# Top.net
KiCad netlist of a schematic drawn in EAGLE
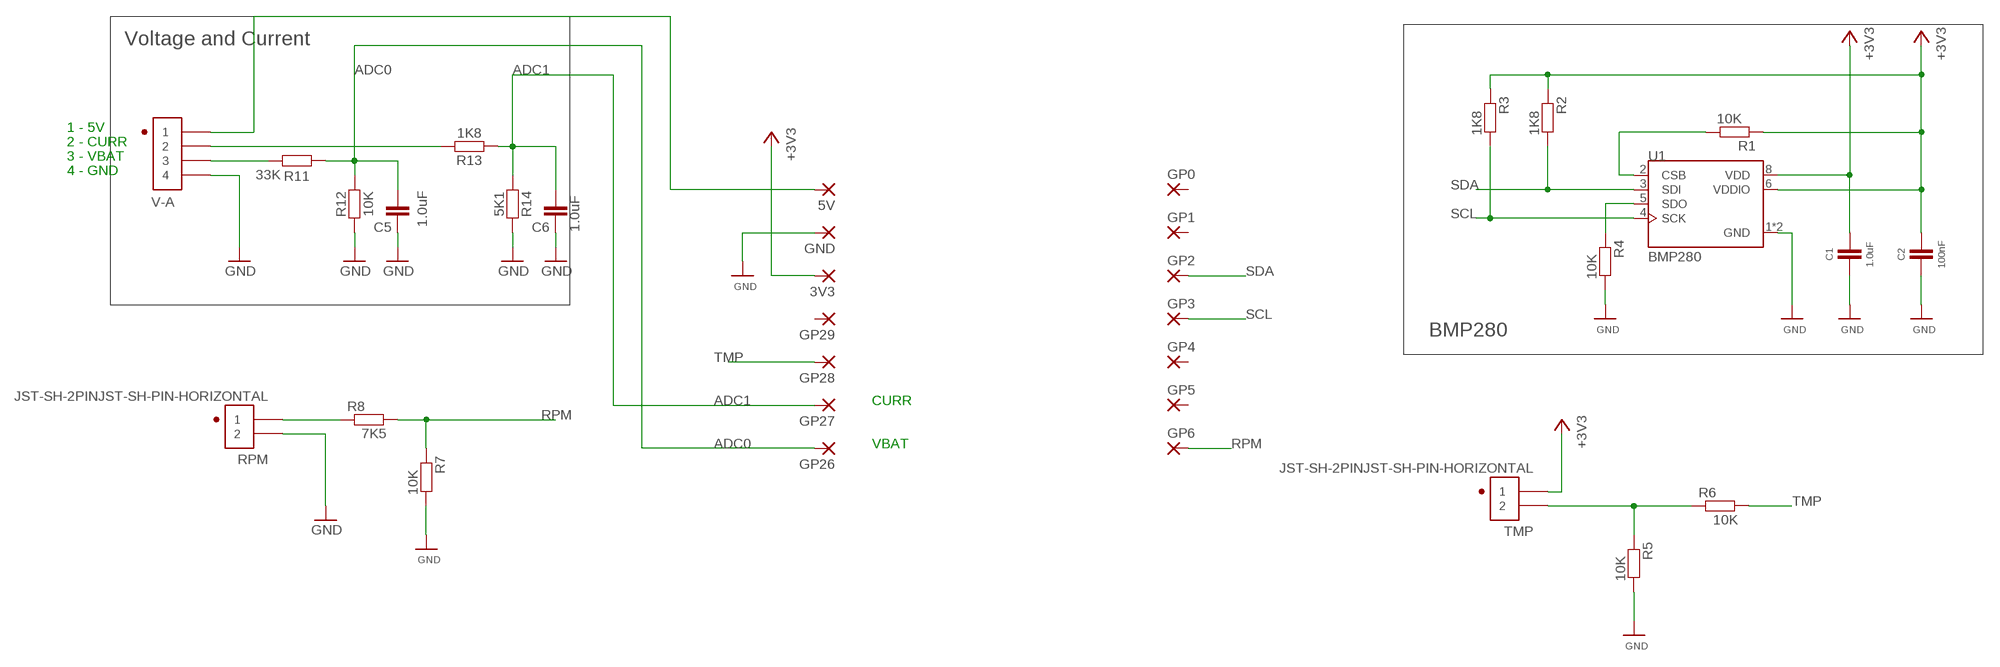
[diagram p0: schematic, sheet 1]

(export (version "E")
  (design (tool "Eeschema 10.0.6"))
  (components
    (comp (ref "3V3")
      (value "1,6/0,9")
      (footprint "eagle-import:1,6_0,9")
      (libsource (lib "eagle-import") (part "1,6/0,9"))
    )
    (comp (ref "5V")
      (value "1,6/0,9")
      (footprint "eagle-import:1,6_0,9")
      (libsource (lib "eagle-import") (part "1,6/0,9"))
    )
    (comp (ref "C1")
      (value "1.0uF")
      (footprint "eagle-import:0402")
      (libsource (lib "eagle-import") (part "1.0UF-0402-16V-10%"))
    )
    (comp (ref "C2")
      (value "100nF")
      (footprint "eagle-import:0603")
      (libsource (lib "eagle-import") (part "1.0UF-0603-16V-10%"))
    )
    (comp (ref "C5")
      (value "1.0uF")
      (footprint "eagle-import:0603")
      (libsource (lib "eagle-import") (part "1.0UF-0603-16V-10%-X7R"))
    )
    (comp (ref "C6")
      (value "1.0uF")
      (footprint "eagle-import:0603")
      (libsource (lib "eagle-import") (part "1.0UF-0603-16V-10%-X7R"))
    )
    (comp (ref "GND")
      (value "1,6/0,9")
      (footprint "eagle-import:1,6_0,9")
      (libsource (lib "eagle-import") (part "1,6/0,9"))
    )
    (comp (ref "GP0")
      (value "1,6/0,9")
      (footprint "eagle-import:1,6_0,9")
      (libsource (lib "eagle-import") (part "1,6/0,9"))
    )
    (comp (ref "GP1")
      (value "1,6/0,9")
      (footprint "eagle-import:1,6_0,9")
      (libsource (lib "eagle-import") (part "1,6/0,9"))
    )
    (comp (ref "GP2")
      (value "1,6/0,9")
      (footprint "eagle-import:1,6_0,9")
      (libsource (lib "eagle-import") (part "1,6/0,9"))
    )
    (comp (ref "GP3")
      (value "1,6/0,9")
      (footprint "eagle-import:1,6_0,9")
      (libsource (lib "eagle-import") (part "1,6/0,9"))
    )
    (comp (ref "GP4")
      (value "1,6/0,9")
      (footprint "eagle-import:1,6_0,9")
      (libsource (lib "eagle-import") (part "1,6/0,9"))
    )
    (comp (ref "GP5")
      (value "1,6/0,9")
      (footprint "eagle-import:1,6_0,9")
      (libsource (lib "eagle-import") (part "1,6/0,9"))
    )
    (comp (ref "GP6")
      (value "1,6/0,9")
      (footprint "eagle-import:1,6_0,9")
      (libsource (lib "eagle-import") (part "1,6/0,9"))
    )
    (comp (ref "GP26")
      (value "1,6/0,9")
      (footprint "eagle-import:1,6_0,9")
      (libsource (lib "eagle-import") (part "1,6/0,9"))
    )
    (comp (ref "GP27")
      (value "1,6/0,9")
      (footprint "eagle-import:1,6_0,9")
      (libsource (lib "eagle-import") (part "1,6/0,9"))
    )
    (comp (ref "GP28")
      (value "1,6/0,9")
      (footprint "eagle-import:1,6_0,9")
      (libsource (lib "eagle-import") (part "1,6/0,9"))
    )
    (comp (ref "GP29")
      (value "1,6/0,9")
      (footprint "eagle-import:1,6_0,9")
      (libsource (lib "eagle-import") (part "1,6/0,9"))
    )
    (comp (ref "R1")
      (value "10K")
      (footprint "eagle-import:0603")
      (libsource (lib "eagle-import") (part "RESISTOR0603"))
    )
    (comp (ref "R2")
      (value "1K8")
      (footprint "eagle-import:0603")
      (libsource (lib "eagle-import") (part "RESISTOR0603"))
    )
    (comp (ref "R3")
      (value "1K8")
      (footprint "eagle-import:0603")
      (libsource (lib "eagle-import") (part "RESISTOR0603"))
    )
    (comp (ref "R4")
      (value "10K")
      (footprint "eagle-import:0603")
      (libsource (lib "eagle-import") (part "RESISTOR0603"))
    )
    (comp (ref "R5")
      (value "10K")
      (footprint "eagle-import:0603")
      (libsource (lib "eagle-import") (part "RESISTOR0603"))
    )
    (comp (ref "R6")
      (value "10K")
      (footprint "eagle-import:0603")
      (libsource (lib "eagle-import") (part "RESISTOR0603"))
    )
    (comp (ref "R7")
      (value "10K")
      (footprint "eagle-import:0603")
      (libsource (lib "eagle-import") (part "RESISTOR0603"))
    )
    (comp (ref "R8")
      (value "7K5")
      (footprint "eagle-import:0603")
      (libsource (lib "eagle-import") (part "RESISTOR0603"))
    )
    (comp (ref "R11")
      (value "33K")
      (footprint "eagle-import:0603")
      (libsource (lib "eagle-import") (part "RESISTOR0603"))
    )
    (comp (ref "R12")
      (value "10K")
      (footprint "eagle-import:0603")
      (libsource (lib "eagle-import") (part "RESISTOR0603"))
    )
    (comp (ref "R13")
      (value "1K8")
      (footprint "eagle-import:0603")
      (libsource (lib "eagle-import") (part "RESISTOR0603"))
    )
    (comp (ref "R14")
      (value "5K1")
      (footprint "eagle-import:0603")
      (libsource (lib "eagle-import") (part "RESISTOR0603"))
    )
    (comp (ref "RPM")
      (value "JST-SH-2PINJST-SH-PIN-HORIZONTAL")
      (footprint "eagle-import:JST-SH-2PIN-1.0MM")
      (libsource (lib "eagle-import") (part "JST-SH-2PINJST-SH-PIN-HORIZONTAL"))
    )
    (comp (ref "TMP")
      (value "JST-SH-2PINJST-SH-PIN-HORIZONTAL")
      (footprint "eagle-import:JST-SH-2PIN-1.0MM")
      (libsource (lib "eagle-import") (part "JST-SH-2PINJST-SH-PIN-HORIZONTAL"))
    )
    (comp (ref "U1")
      (value "BMP280")
      (footprint "eagle-import:XDCR_BMP280")
      (fields (field (name "MF") "Bosch"))
      (libsource (lib "eagle-import") (part "BMP280"))
    )
    (comp (ref "V-A")
      (value "JST-SH-4PINJST-SH-4-HORIZONTAL")
      (footprint "eagle-import:JST-SH-4PIN-1.0MM")
      (libsource (lib "eagle-import") (part "JST-SH-4PINJST-SH-4-HORIZONTAL"))
    )
  )
  (nets
    (net (code "1") (name "+3V3") (class "Default")
      (node (ref "3V3") (pin "1") (pinfunction "P_1") (pintype "passive"))
      (node (ref "C1") (pin "1") (pinfunction "1_1") (pintype "passive"))
      (node (ref "C2") (pin "1") (pinfunction "1_1") (pintype "passive"))
      (node (ref "R1") (pin "1") (pinfunction "1_1") (pintype "passive"))
      (node (ref "R2") (pin "1") (pinfunction "1_1") (pintype "passive"))
      (node (ref "R3") (pin "1") (pinfunction "1_1") (pintype "passive"))
      (node (ref "TMP") (pin "1") (pinfunction "1_1") (pintype "bidirectional"))
      (node (ref "U1") (pin "6") (pinfunction "VDDIO_6") (pintype "power_in"))
      (node (ref "U1") (pin "8") (pinfunction "VDD_8") (pintype "power_in"))
    )
    (net (code "2") (name "/ADC0") (class "Default")
      (node (ref "C5") (pin "2") (pinfunction "2_2") (pintype "passive"))
      (node (ref "GP26") (pin "1") (pinfunction "P_1") (pintype "passive"))
      (node (ref "R11") (pin "2") (pinfunction "2_2") (pintype "passive"))
      (node (ref "R12") (pin "2") (pinfunction "2_2") (pintype "passive"))
    )
    (net (code "3") (name "/ADC1") (class "Default")
      (node (ref "C6") (pin "2") (pinfunction "2_2") (pintype "passive"))
      (node (ref "GP27") (pin "1") (pinfunction "P_1") (pintype "passive"))
      (node (ref "R13") (pin "1") (pinfunction "1_1") (pintype "passive"))
      (node (ref "R14") (pin "1") (pinfunction "1_1") (pintype "passive"))
    )
    (net (code "4") (name "/RPM") (class "Default")
      (node (ref "GP6") (pin "1") (pinfunction "P_1") (pintype "passive"))
      (node (ref "R7") (pin "1") (pinfunction "1_1") (pintype "passive"))
      (node (ref "R8") (pin "2") (pinfunction "2_2") (pintype "passive"))
    )
    (net (code "5") (name "/SCL") (class "Default")
      (node (ref "GP3") (pin "1") (pinfunction "P_1") (pintype "passive"))
      (node (ref "R3") (pin "2") (pinfunction "2_2") (pintype "passive"))
      (node (ref "U1") (pin "4") (pinfunction "SCK_4") (pintype "input"))
    )
    (net (code "6") (name "/SDA") (class "Default")
      (node (ref "GP2") (pin "1") (pinfunction "P_1") (pintype "passive"))
      (node (ref "R2") (pin "2") (pinfunction "2_2") (pintype "passive"))
      (node (ref "U1") (pin "3") (pinfunction "SDI_3") (pintype "bidirectional"))
    )
    (net (code "7") (name "/TMP") (class "Default")
      (node (ref "GP28") (pin "1") (pinfunction "P_1") (pintype "passive"))
      (node (ref "R6") (pin "2") (pinfunction "2_2") (pintype "passive"))
    )
    (net (code "8") (name "GND") (class "Default")
      (node (ref "C1") (pin "2") (pinfunction "2_2") (pintype "passive"))
      (node (ref "C2") (pin "2") (pinfunction "2_2") (pintype "passive"))
      (node (ref "C5") (pin "1") (pinfunction "1_1") (pintype "passive"))
      (node (ref "C6") (pin "1") (pinfunction "1_1") (pintype "passive"))
      (node (ref "GND") (pin "1") (pinfunction "P_1") (pintype "passive"))
      (node (ref "R12") (pin "1") (pinfunction "1_1") (pintype "passive"))
      (node (ref "R14") (pin "2") (pinfunction "2_2") (pintype "passive"))
      (node (ref "R4") (pin "2") (pinfunction "2_2") (pintype "passive"))
      (node (ref "R5") (pin "2") (pinfunction "2_2") (pintype "passive"))
      (node (ref "R7") (pin "2") (pinfunction "2_2") (pintype "passive"))
      (node (ref "RPM") (pin "2") (pinfunction "2_2") (pintype "bidirectional"))
      (node (ref "U1") (pin "1") (pinfunction "GND_1") (pintype "power_in"))
      (node (ref "U1") (pin "7") (pinfunction "GND_7") (pintype "power_in"))
      (node (ref "V-A") (pin "4") (pinfunction "4_4") (pintype "bidirectional"))
    )
    (net (code "9") (name "Net-(5V-P)") (class "Default")
      (node (ref "5V") (pin "1") (pinfunction "P_1") (pintype "passive"))
      (node (ref "V-A") (pin "1") (pinfunction "1_1") (pintype "bidirectional"))
    )
    (net (code "10") (name "Net-(R5-Pad1)") (class "Default")
      (node (ref "R5") (pin "1") (pinfunction "1_1") (pintype "passive"))
      (node (ref "R6") (pin "1") (pinfunction "1_1") (pintype "passive"))
      (node (ref "TMP") (pin "2") (pinfunction "2_2") (pintype "bidirectional"))
    )
    (net (code "11") (name "Net-(R8-Pad1)") (class "Default")
      (node (ref "R8") (pin "1") (pinfunction "1_1") (pintype "passive"))
      (node (ref "RPM") (pin "1") (pinfunction "1_1") (pintype "bidirectional"))
    )
    (net (code "12") (name "Net-(R11-Pad1)") (class "Default")
      (node (ref "R11") (pin "1") (pinfunction "1_1") (pintype "passive"))
      (node (ref "V-A") (pin "3") (pinfunction "3_3") (pintype "bidirectional"))
    )
    (net (code "13") (name "Net-(R13-Pad2)") (class "Default")
      (node (ref "R13") (pin "2") (pinfunction "2_2") (pintype "passive"))
      (node (ref "V-A") (pin "2") (pinfunction "2_2") (pintype "bidirectional"))
    )
    (net (code "14") (name "Net-(U1-CSB)") (class "Default")
      (node (ref "R1") (pin "2") (pinfunction "2_2") (pintype "passive"))
      (node (ref "U1") (pin "2") (pinfunction "CSB_2") (pintype "input"))
    )
    (net (code "15") (name "Net-(U1-SDO)") (class "Default")
      (node (ref "R4") (pin "1") (pinfunction "1_1") (pintype "passive"))
      (node (ref "U1") (pin "5") (pinfunction "SDO_5") (pintype "bidirectional"))
    )
    (net (code "16") (name "unconnected-(GP0-P-Pad1)") (class "Default")
      (node (ref "GP0") (pin "1") (pinfunction "P_1") (pintype "passive"))
    )
    (net (code "17") (name "unconnected-(GP1-P-Pad1)") (class "Default")
      (node (ref "GP1") (pin "1") (pinfunction "P_1") (pintype "passive"))
    )
    (net (code "18") (name "unconnected-(GP4-P-Pad1)") (class "Default")
      (node (ref "GP4") (pin "1") (pinfunction "P_1") (pintype "passive"))
    )
    (net (code "19") (name "unconnected-(GP5-P-Pad1)") (class "Default")
      (node (ref "GP5") (pin "1") (pinfunction "P_1") (pintype "passive"))
    )
    (net (code "20") (name "unconnected-(GP29-P-Pad1)") (class "Default")
      (node (ref "GP29") (pin "1") (pinfunction "P_1") (pintype "passive"))
    )
  )
)
